# fpga-serdes.net
KiCad netlist of a schematic drawn in Altium Designer
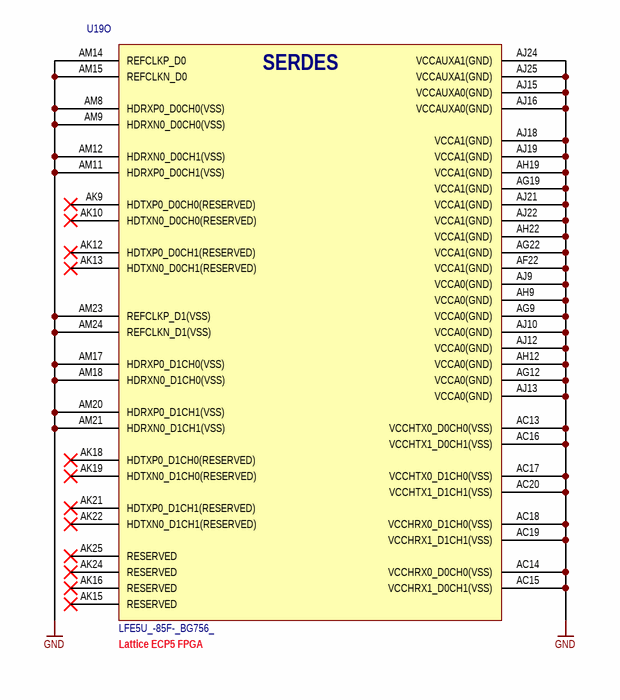
[diagram p0: fpga-serdes.SchDoc]

(export (version "E")
  (design (tool "Eeschema 10.0.6"))
  (components
    (comp (ref "U19")
      (value "LFE5U_-85F-_BG756_")
      (footprint "lattice:caBGA756")
      (description "ECP5 FPGA, 85k LUT, 756-caBGA")
      (fields (field (name "MANUFACTURER") "Lattice Semiconductor"))
      (libsource (lib "lattice") (part "LFE5U_-85F-_BG756_"))
    )
  )
  (nets
    (net (code "1") (name "GND") (class "Default")
      (node (ref "U19") (pin "AC13") (pinfunction "VCCHTX0_D0CH0(VSS)_AC13") (pintype "power_in"))
      (node (ref "U19") (pin "AC14") (pinfunction "VCCHRX0_D0CH0(VSS)_AC14") (pintype "power_in"))
      (node (ref "U19") (pin "AC15") (pinfunction "VCCHRX1_D0CH1(VSS)_AC15") (pintype "power_in"))
      (node (ref "U19") (pin "AC16") (pinfunction "VCCHTX1_D0CH1(VSS)_AC16") (pintype "power_in"))
      (node (ref "U19") (pin "AC17") (pinfunction "VCCHTX0_D1CH0(VSS)_AC17") (pintype "power_in"))
      (node (ref "U19") (pin "AC18") (pinfunction "VCCHRX0_D1CH0(VSS)_AC18") (pintype "power_in"))
      (node (ref "U19") (pin "AC19") (pinfunction "VCCHRX1_D1CH1(VSS)_AC19") (pintype "power_in"))
      (node (ref "U19") (pin "AC20") (pinfunction "VCCHTX1_D1CH1(VSS)_AC20") (pintype "power_in"))
      (node (ref "U19") (pin "AF22") (pinfunction "VCCA1(GND)_AF22") (pintype "power_in"))
      (node (ref "U19") (pin "AG12") (pinfunction "VCCA0(GND)_AG12") (pintype "power_in"))
      (node (ref "U19") (pin "AG19") (pinfunction "VCCA1(GND)_AG19") (pintype "power_in"))
      (node (ref "U19") (pin "AG22") (pinfunction "VCCA1(GND)_AG22") (pintype "power_in"))
      (node (ref "U19") (pin "AG9") (pinfunction "VCCA0(GND)_AG9") (pintype "power_in"))
      (node (ref "U19") (pin "AH12") (pinfunction "VCCA0(GND)_AH12") (pintype "power_in"))
      (node (ref "U19") (pin "AH19") (pinfunction "VCCA1(GND)_AH19") (pintype "power_in"))
      (node (ref "U19") (pin "AH22") (pinfunction "VCCA1(GND)_AH22") (pintype "power_in"))
      (node (ref "U19") (pin "AH9") (pinfunction "VCCA0(GND)_AH9") (pintype "power_in"))
      (node (ref "U19") (pin "AJ10") (pinfunction "VCCA0(GND)_AJ10") (pintype "power_in"))
      (node (ref "U19") (pin "AJ12") (pinfunction "VCCA0(GND)_AJ12") (pintype "power_in"))
      (node (ref "U19") (pin "AJ13") (pinfunction "VCCA0(GND)_AJ13") (pintype "power_in"))
      (node (ref "U19") (pin "AJ15") (pinfunction "VCCAUXA0(GND)_AJ15") (pintype "power_in"))
      (node (ref "U19") (pin "AJ16") (pinfunction "VCCAUXA0(GND)_AJ16") (pintype "power_in"))
      (node (ref "U19") (pin "AJ18") (pinfunction "VCCA1(GND)_AJ18") (pintype "power_in"))
      (node (ref "U19") (pin "AJ19") (pinfunction "VCCA1(GND)_AJ19") (pintype "power_in"))
      (node (ref "U19") (pin "AJ21") (pinfunction "VCCA1(GND)_AJ21") (pintype "power_in"))
      (node (ref "U19") (pin "AJ22") (pinfunction "VCCA1(GND)_AJ22") (pintype "power_in"))
      (node (ref "U19") (pin "AJ24") (pinfunction "VCCAUXA1(GND)_AJ24") (pintype "power_in"))
      (node (ref "U19") (pin "AJ25") (pinfunction "VCCAUXA1(GND)_AJ25") (pintype "power_in"))
      (node (ref "U19") (pin "AJ9") (pinfunction "VCCA0(GND)_AJ9") (pintype "power_in"))
      (node (ref "U19") (pin "AM11") (pinfunction "HDRXP0_D0CH1(VSS)_AM11") (pintype "passive"))
      (node (ref "U19") (pin "AM12") (pinfunction "HDRXN0_D0CH1(VSS)_AM12") (pintype "passive"))
      (node (ref "U19") (pin "AM14") (pinfunction "REFCLKP_D0_AM14") (pintype "passive"))
      (node (ref "U19") (pin "AM15") (pinfunction "REFCLKN_D0_AM15") (pintype "passive"))
      (node (ref "U19") (pin "AM17") (pinfunction "HDRXP0_D1CH0(VSS)_AM17") (pintype "passive"))
      (node (ref "U19") (pin "AM18") (pinfunction "HDRXN0_D1CH0(VSS)_AM18") (pintype "passive"))
      (node (ref "U19") (pin "AM20") (pinfunction "HDRXP0_D1CH1(VSS)_AM20") (pintype "passive"))
      (node (ref "U19") (pin "AM21") (pinfunction "HDRXN0_D1CH1(VSS)_AM21") (pintype "passive"))
      (node (ref "U19") (pin "AM23") (pinfunction "REFCLKP_D1(VSS)_AM23") (pintype "passive"))
      (node (ref "U19") (pin "AM24") (pinfunction "REFCLKN_D1(VSS)_AM24") (pintype "passive"))
      (node (ref "U19") (pin "AM8") (pinfunction "HDRXP0_D0CH0(VSS)_AM8") (pintype "passive"))
      (node (ref "U19") (pin "AM9") (pinfunction "HDRXN0_D0CH0(VSS)_AM9") (pintype "passive"))
    )
    (net (code "2") (name "unconnected-(U19O-HDTXN0_D0CH0(RESERVED)-PadAK10)") (class "Default")
      (node (ref "U19") (pin "AK10") (pinfunction "HDTXN0_D0CH0(RESERVED)_AK10") (pintype "passive+no_connect"))
    )
    (net (code "3") (name "unconnected-(U19O-HDTXN0_D0CH1(RESERVED)-PadAK13)") (class "Default")
      (node (ref "U19") (pin "AK13") (pinfunction "HDTXN0_D0CH1(RESERVED)_AK13") (pintype "passive+no_connect"))
    )
    (net (code "4") (name "unconnected-(U19O-HDTXN0_D1CH0(RESERVED)-PadAK19)") (class "Default")
      (node (ref "U19") (pin "AK19") (pinfunction "HDTXN0_D1CH0(RESERVED)_AK19") (pintype "passive+no_connect"))
    )
    (net (code "5") (name "unconnected-(U19O-HDTXN0_D1CH1(RESERVED)-PadAK22)") (class "Default")
      (node (ref "U19") (pin "AK22") (pinfunction "HDTXN0_D1CH1(RESERVED)_AK22") (pintype "passive+no_connect"))
    )
    (net (code "6") (name "unconnected-(U19O-HDTXP0_D0CH0(RESERVED)-PadAK9)") (class "Default")
      (node (ref "U19") (pin "AK9") (pinfunction "HDTXP0_D0CH0(RESERVED)_AK9") (pintype "passive+no_connect"))
    )
    (net (code "7") (name "unconnected-(U19O-HDTXP0_D0CH1(RESERVED)-PadAK12)") (class "Default")
      (node (ref "U19") (pin "AK12") (pinfunction "HDTXP0_D0CH1(RESERVED)_AK12") (pintype "passive+no_connect"))
    )
    (net (code "8") (name "unconnected-(U19O-HDTXP0_D1CH0(RESERVED)-PadAK18)") (class "Default")
      (node (ref "U19") (pin "AK18") (pinfunction "HDTXP0_D1CH0(RESERVED)_AK18") (pintype "passive+no_connect"))
    )
    (net (code "9") (name "unconnected-(U19O-HDTXP0_D1CH1(RESERVED)-PadAK21)") (class "Default")
      (node (ref "U19") (pin "AK21") (pinfunction "HDTXP0_D1CH1(RESERVED)_AK21") (pintype "passive+no_connect"))
    )
    (net (code "10") (name "unconnected-(U19O-RESERVED-PadAK15)") (class "Default")
      (node (ref "U19") (pin "AK15") (pinfunction "RESERVED_AK15") (pintype "passive+no_connect"))
    )
    (net (code "11") (name "unconnected-(U19O-RESERVED-PadAK16)") (class "Default")
      (node (ref "U19") (pin "AK16") (pinfunction "RESERVED_AK16") (pintype "passive+no_connect"))
    )
    (net (code "12") (name "unconnected-(U19O-RESERVED-PadAK24)") (class "Default")
      (node (ref "U19") (pin "AK24") (pinfunction "RESERVED_AK24") (pintype "passive+no_connect"))
    )
    (net (code "13") (name "unconnected-(U19O-RESERVED-PadAK25)") (class "Default")
      (node (ref "U19") (pin "AK25") (pinfunction "RESERVED_AK25") (pintype "passive+no_connect"))
    )
  )
)
